# MCU.net
KiCad netlist of a schematic drawn in Altium Designer
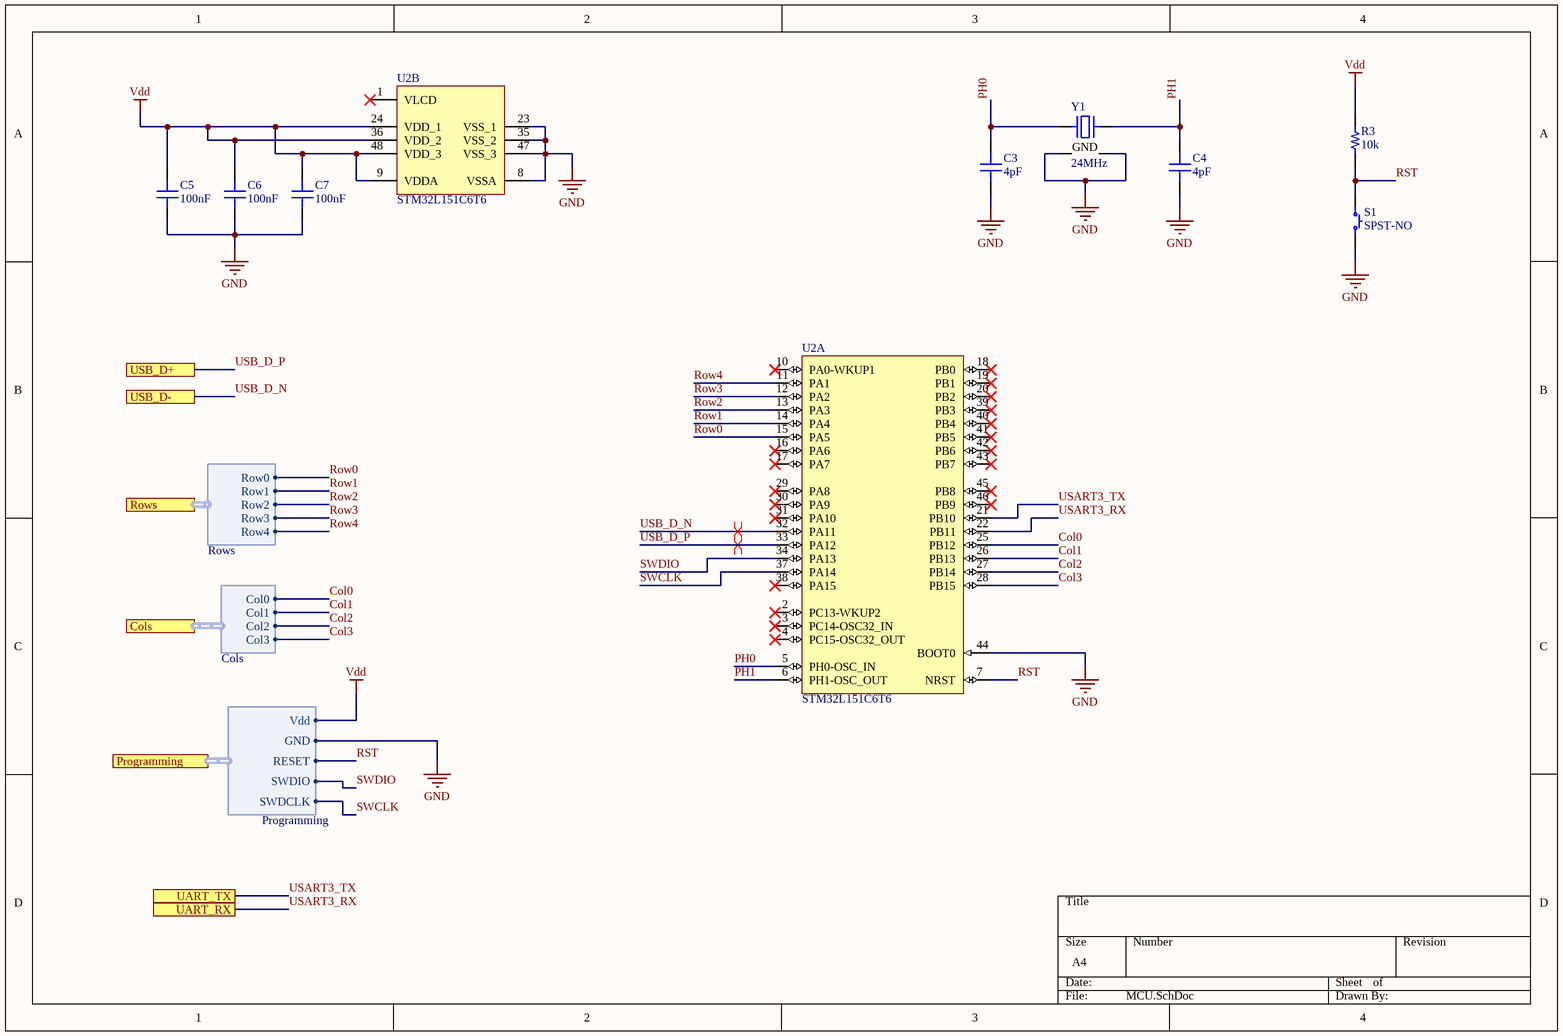
[diagram p0: MCU.SchDoc]

(export (version "E")
  (design (tool "Eeschema 10.0.6"))
  (components
    (comp (ref "C3")
      (value "4pF")
      (footprint "CAP 0603_1608")
      (description "SMT Capacitor")
      (libsource (lib "SCH - PASSIVES - CAPACITOR") (part "Capacitor"))
    )
    (comp (ref "C4")
      (value "4pF")
      (footprint "CAP 0603_1608")
      (description "SMT Capacitor")
      (libsource (lib "SCH - PASSIVES - CAPACITOR") (part "Capacitor"))
    )
    (comp (ref "C5")
      (value "100nF")
      (footprint "CAP 0603_1608")
      (description "SMT Capacitor")
      (libsource (lib "SCH - PASSIVES - CAPACITOR") (part "Capacitor"))
    )
    (comp (ref "C6")
      (value "100nF")
      (footprint "CAP 0603_1608")
      (description "SMT Capacitor")
      (libsource (lib "SCH - PASSIVES - CAPACITOR") (part "Capacitor"))
    )
    (comp (ref "C7")
      (value "100nF")
      (footprint "CAP 0603_1608")
      (description "SMT Capacitor")
      (libsource (lib "SCH - PASSIVES - CAPACITOR") (part "Capacitor"))
    )
    (comp (ref "R3")
      (value "10k")
      (footprint "RES 0603_1608")
      (description "SMT Resistor")
      (libsource (lib "SCH - PASSIVES - RESISTOR") (part "Resistor"))
    )
    (comp (ref "S1")
      (value "SPST-NO")
      (footprint "TE FSMSMTR")
      (libsource (lib "SCH - BUTTON - SPST-NO 2 PIN") (part "SPST-NO 2 PIN"))
    )
    (comp (ref "U2")
      (value "STM32L151C6T6")
      (footprint "STM-LQFP48_M")
      (libsource (lib "Altium Content Vault") (part "MC-ARM-STM32L15XX6_8_B-SQ48"))
    )
    (comp (ref "Y1")
      (value "24MHz")
      (footprint "ABRACON ABM10")
      (description "SMT Crystal")
      (libsource (lib "SCH - CRYSTALS - ABRACON CRYSTAL ABM10") (part "Abracon Crystal ABM10"))
    )
  )
  (nets
    (net (code "4") (name "/Col0") (class "Default")
      (node (ref "U2") (pin "25") (pinfunction "PB12_25") (pintype "bidirectional"))
    )
    (net (code "5") (name "/Col1") (class "Default")
      (node (ref "U2") (pin "26") (pinfunction "PB13_26") (pintype "bidirectional"))
    )
    (net (code "6") (name "/Col2") (class "Default")
      (node (ref "U2") (pin "27") (pinfunction "PB14_27") (pintype "bidirectional"))
    )
    (net (code "7") (name "/Col3") (class "Default")
      (node (ref "U2") (pin "28") (pinfunction "PB15_28") (pintype "bidirectional"))
    )
    (net (code "8") (name "/PH0") (class "Default")
      (node (ref "C3") (pin "2") (pinfunction "2_2") (pintype "passive"))
      (node (ref "U2") (pin "5") (pinfunction "PH0-OSC_IN_5") (pintype "bidirectional"))
      (node (ref "Y1") (pin "1") (pinfunction "1_1") (pintype "passive"))
    )
    (net (code "9") (name "/PH1") (class "Default")
      (node (ref "C4") (pin "2") (pinfunction "2_2") (pintype "passive"))
      (node (ref "U2") (pin "6") (pinfunction "PH1-OSC_OUT_6") (pintype "bidirectional"))
      (node (ref "Y1") (pin "3") (pinfunction "3_3") (pintype "passive"))
    )
    (net (code "10") (name "/RST") (class "Default")
      (node (ref "R3") (pin "1") (pinfunction "1_1") (pintype "passive"))
      (node (ref "S1") (pin "1") (pinfunction "1_1") (pintype "passive"))
      (node (ref "U2") (pin "7") (pinfunction "NRST_7") (pintype "bidirectional"))
    )
    (net (code "11") (name "/Row0") (class "Default")
      (node (ref "U2") (pin "15") (pinfunction "PA5_15") (pintype "bidirectional"))
    )
    (net (code "12") (name "/Row1") (class "Default")
      (node (ref "U2") (pin "14") (pinfunction "PA4_14") (pintype "bidirectional"))
    )
    (net (code "13") (name "/Row2") (class "Default")
      (node (ref "U2") (pin "13") (pinfunction "PA3_13") (pintype "bidirectional"))
    )
    (net (code "14") (name "/Row3") (class "Default")
      (node (ref "U2") (pin "12") (pinfunction "PA2_12") (pintype "bidirectional"))
    )
    (net (code "15") (name "/Row4") (class "Default")
      (node (ref "U2") (pin "11") (pinfunction "PA1_11") (pintype "bidirectional"))
    )
    (net (code "16") (name "/SWCLK") (class "Default")
      (node (ref "U2") (pin "37") (pinfunction "PA14_37") (pintype "bidirectional"))
    )
    (net (code "17") (name "/SWDIO") (class "Default")
      (node (ref "U2") (pin "34") (pinfunction "PA13_34") (pintype "bidirectional"))
    )
    (net (code "18") (name "/USART3_RX") (class "Default")
      (node (ref "U2") (pin "22") (pinfunction "PB11_22") (pintype "bidirectional"))
    )
    (net (code "19") (name "/USART3_TX") (class "Default")
      (node (ref "U2") (pin "21") (pinfunction "PB10_21") (pintype "bidirectional"))
    )
    (net (code "20") (name "/USB_D_N") (class "Default")
      (node (ref "U2") (pin "32") (pinfunction "PA11_32") (pintype "bidirectional"))
    )
    (net (code "21") (name "/USB_D_P") (class "Default")
      (node (ref "U2") (pin "33") (pinfunction "PA12_33") (pintype "bidirectional"))
    )
    (net (code "25") (name "GND") (class "Default")
      (node (ref "C3") (pin "1") (pinfunction "1_1") (pintype "passive"))
      (node (ref "C4") (pin "1") (pinfunction "1_1") (pintype "passive"))
      (node (ref "C5") (pin "1") (pinfunction "1_1") (pintype "passive"))
      (node (ref "C6") (pin "1") (pinfunction "1_1") (pintype "passive"))
      (node (ref "C7") (pin "1") (pinfunction "1_1") (pintype "passive"))
      (node (ref "S1") (pin "2") (pinfunction "2_2") (pintype "passive"))
      (node (ref "U2") (pin "23") (pinfunction "VSS_1_23") (pintype "power_in"))
      (node (ref "U2") (pin "35") (pinfunction "VSS_2_35") (pintype "power_in"))
      (node (ref "U2") (pin "44") (pinfunction "BOOT0_44") (pintype "input"))
      (node (ref "U2") (pin "47") (pinfunction "VSS_3_47") (pintype "power_in"))
      (node (ref "U2") (pin "8") (pinfunction "VSSA_8") (pintype "power_in"))
      (node (ref "Y1") (pin "2") (pinfunction "GND_2") (pintype "passive"))
      (node (ref "Y1") (pin "4") (pinfunction "GND_4") (pintype "passive"))
    )
    (net (code "26") (name "Vdd") (class "Default")
      (node (ref "C5") (pin "2") (pinfunction "2_2") (pintype "passive"))
      (node (ref "C6") (pin "2") (pinfunction "2_2") (pintype "passive"))
      (node (ref "C7") (pin "2") (pinfunction "2_2") (pintype "passive"))
      (node (ref "R3") (pin "2") (pinfunction "2_2") (pintype "passive"))
      (node (ref "U2") (pin "24") (pinfunction "VDD_1_24") (pintype "power_in"))
      (node (ref "U2") (pin "36") (pinfunction "VDD_2_36") (pintype "power_in"))
      (node (ref "U2") (pin "48") (pinfunction "VDD_3_48") (pintype "power_in"))
      (node (ref "U2") (pin "9") (pinfunction "VDDA_9") (pintype "power_in"))
    )
    (net (code "27") (name "unconnected-(U2A-PA0-WKUP1-Pad10)") (class "Default")
      (node (ref "U2") (pin "10") (pinfunction "PA0-WKUP1_10") (pintype "bidirectional+no_connect"))
    )
    (net (code "28") (name "unconnected-(U2A-PA6-Pad16)") (class "Default")
      (node (ref "U2") (pin "16") (pinfunction "PA6_16") (pintype "bidirectional+no_connect"))
    )
    (net (code "29") (name "unconnected-(U2A-PA7-Pad17)") (class "Default")
      (node (ref "U2") (pin "17") (pinfunction "PA7_17") (pintype "bidirectional+no_connect"))
    )
    (net (code "30") (name "unconnected-(U2A-PA8-Pad29)") (class "Default")
      (node (ref "U2") (pin "29") (pinfunction "PA8_29") (pintype "bidirectional+no_connect"))
    )
    (net (code "31") (name "unconnected-(U2A-PA9-Pad30)") (class "Default")
      (node (ref "U2") (pin "30") (pinfunction "PA9_30") (pintype "bidirectional+no_connect"))
    )
    (net (code "32") (name "unconnected-(U2A-PA10-Pad31)") (class "Default")
      (node (ref "U2") (pin "31") (pinfunction "PA10_31") (pintype "bidirectional+no_connect"))
    )
    (net (code "33") (name "unconnected-(U2A-PA15-Pad38)") (class "Default")
      (node (ref "U2") (pin "38") (pinfunction "PA15_38") (pintype "bidirectional+no_connect"))
    )
    (net (code "34") (name "unconnected-(U2A-PB0-Pad18)") (class "Default")
      (node (ref "U2") (pin "18") (pinfunction "PB0_18") (pintype "bidirectional+no_connect"))
    )
    (net (code "35") (name "unconnected-(U2A-PB1-Pad19)") (class "Default")
      (node (ref "U2") (pin "19") (pinfunction "PB1_19") (pintype "bidirectional+no_connect"))
    )
    (net (code "36") (name "unconnected-(U2A-PB2-Pad20)") (class "Default")
      (node (ref "U2") (pin "20") (pinfunction "PB2_20") (pintype "bidirectional+no_connect"))
    )
    (net (code "37") (name "unconnected-(U2A-PB3-Pad39)") (class "Default")
      (node (ref "U2") (pin "39") (pinfunction "PB3_39") (pintype "bidirectional+no_connect"))
    )
    (net (code "38") (name "unconnected-(U2A-PB4-Pad40)") (class "Default")
      (node (ref "U2") (pin "40") (pinfunction "PB4_40") (pintype "bidirectional+no_connect"))
    )
    (net (code "39") (name "unconnected-(U2A-PB5-Pad41)") (class "Default")
      (node (ref "U2") (pin "41") (pinfunction "PB5_41") (pintype "bidirectional+no_connect"))
    )
    (net (code "40") (name "unconnected-(U2A-PB6-Pad42)") (class "Default")
      (node (ref "U2") (pin "42") (pinfunction "PB6_42") (pintype "bidirectional+no_connect"))
    )
    (net (code "41") (name "unconnected-(U2A-PB7-Pad43)") (class "Default")
      (node (ref "U2") (pin "43") (pinfunction "PB7_43") (pintype "bidirectional+no_connect"))
    )
    (net (code "42") (name "unconnected-(U2A-PB8-Pad45)") (class "Default")
      (node (ref "U2") (pin "45") (pinfunction "PB8_45") (pintype "bidirectional+no_connect"))
    )
    (net (code "43") (name "unconnected-(U2A-PB9-Pad46)") (class "Default")
      (node (ref "U2") (pin "46") (pinfunction "PB9_46") (pintype "bidirectional+no_connect"))
    )
    (net (code "44") (name "unconnected-(U2A-PC13-WKUP2-Pad2)") (class "Default")
      (node (ref "U2") (pin "2") (pinfunction "PC13-WKUP2_2") (pintype "bidirectional+no_connect"))
    )
    (net (code "45") (name "unconnected-(U2A-PC14-OSC32_IN-Pad3)") (class "Default")
      (node (ref "U2") (pin "3") (pinfunction "PC14-OSC32_IN_3") (pintype "bidirectional+no_connect"))
    )
    (net (code "46") (name "unconnected-(U2A-PC15-OSC32_OUT-Pad4)") (class "Default")
      (node (ref "U2") (pin "4") (pinfunction "PC15-OSC32_OUT_4") (pintype "bidirectional+no_connect"))
    )
    (net (code "47") (name "unconnected-(U2B-VLCD-Pad1)") (class "Default")
      (node (ref "U2") (pin "1") (pinfunction "VLCD_1") (pintype "power_in+no_connect"))
    )
  )
)
